# ForceBoard.net
KiCad netlist of a schematic drawn in EAGLE
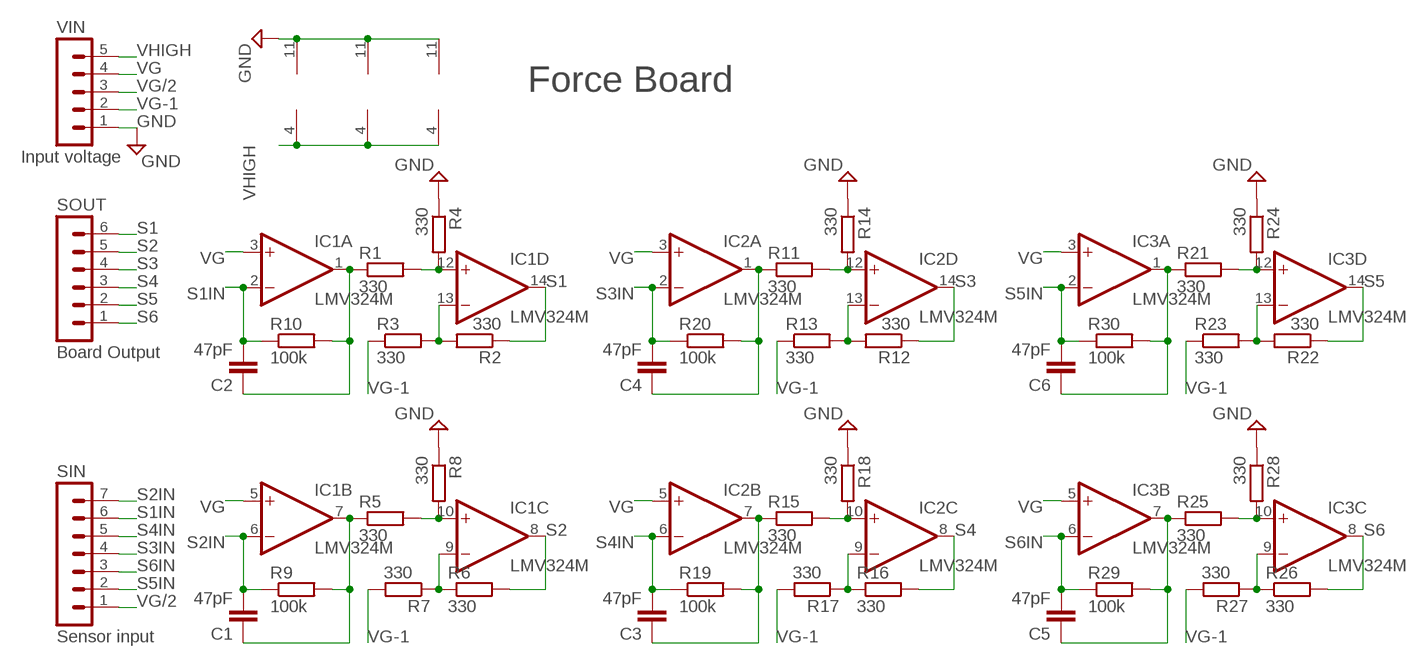
[diagram p0: schematic, sheet 1]

(export (version "E")
  (design (tool "Eeschema 10.0.6"))
  (components
    (comp (ref "C1")
      (value "47pF")
      (footprint "eagle-import:C0805")
      (libsource (lib "eagle-import") (part "C-EUC0805"))
    )
    (comp (ref "C2")
      (value "47pF")
      (footprint "eagle-import:C0805")
      (libsource (lib "eagle-import") (part "C-EUC0805"))
    )
    (comp (ref "C3")
      (value "47pF")
      (footprint "eagle-import:C0805")
      (libsource (lib "eagle-import") (part "C-EUC0805"))
    )
    (comp (ref "C4")
      (value "47pF")
      (footprint "eagle-import:C0805")
      (libsource (lib "eagle-import") (part "C-EUC0805"))
    )
    (comp (ref "C5")
      (value "47pF")
      (footprint "eagle-import:C0805")
      (libsource (lib "eagle-import") (part "C-EUC0805"))
    )
    (comp (ref "C6")
      (value "47pF")
      (footprint "eagle-import:C0805")
      (libsource (lib "eagle-import") (part "C-EUC0805"))
    )
    (comp (ref "IC1")
      (value "LMV324M")
      (footprint "eagle-import:SO14")
      (libsource (lib "eagle-import") (part "LMV324?M"))
    )
    (comp (ref "IC2")
      (value "LMV324M")
      (footprint "eagle-import:SO14")
      (libsource (lib "eagle-import") (part "LMV324?M"))
    )
    (comp (ref "IC3")
      (value "LMV324M")
      (footprint "eagle-import:SO14")
      (libsource (lib "eagle-import") (part "LMV324?M"))
    )
    (comp (ref "R1")
      (value "330")
      (footprint "eagle-import:R0805")
      (libsource (lib "eagle-import") (part "R-EU_R0805"))
    )
    (comp (ref "R2")
      (value "330")
      (footprint "eagle-import:R0805")
      (libsource (lib "eagle-import") (part "R-EU_R0805"))
    )
    (comp (ref "R3")
      (value "330")
      (footprint "eagle-import:R0805")
      (libsource (lib "eagle-import") (part "R-EU_R0805"))
    )
    (comp (ref "R4")
      (value "330")
      (footprint "eagle-import:R0805")
      (libsource (lib "eagle-import") (part "R-EU_R0805"))
    )
    (comp (ref "R5")
      (value "330")
      (footprint "eagle-import:R0805")
      (libsource (lib "eagle-import") (part "R-EU_R0805"))
    )
    (comp (ref "R6")
      (value "330")
      (footprint "eagle-import:R0805")
      (libsource (lib "eagle-import") (part "R-EU_R0805"))
    )
    (comp (ref "R7")
      (value "330")
      (footprint "eagle-import:R0805")
      (libsource (lib "eagle-import") (part "R-EU_R0805"))
    )
    (comp (ref "R8")
      (value "330")
      (footprint "eagle-import:R0805")
      (libsource (lib "eagle-import") (part "R-EU_R0805"))
    )
    (comp (ref "R9")
      (value "100k")
      (footprint "eagle-import:R0805")
      (libsource (lib "eagle-import") (part "R-EU_R0805"))
    )
    (comp (ref "R10")
      (value "100k")
      (footprint "eagle-import:R0805")
      (libsource (lib "eagle-import") (part "R-EU_R0805"))
    )
    (comp (ref "R11")
      (value "330")
      (footprint "eagle-import:R0805")
      (libsource (lib "eagle-import") (part "R-EU_R0805"))
    )
    (comp (ref "R12")
      (value "330")
      (footprint "eagle-import:R0805")
      (libsource (lib "eagle-import") (part "R-EU_R0805"))
    )
    (comp (ref "R13")
      (value "330")
      (footprint "eagle-import:R0805")
      (libsource (lib "eagle-import") (part "R-EU_R0805"))
    )
    (comp (ref "R14")
      (value "330")
      (footprint "eagle-import:R0805")
      (libsource (lib "eagle-import") (part "R-EU_R0805"))
    )
    (comp (ref "R15")
      (value "330")
      (footprint "eagle-import:R0805")
      (libsource (lib "eagle-import") (part "R-EU_R0805"))
    )
    (comp (ref "R16")
      (value "330")
      (footprint "eagle-import:R0805")
      (libsource (lib "eagle-import") (part "R-EU_R0805"))
    )
    (comp (ref "R17")
      (value "330")
      (footprint "eagle-import:R0805")
      (libsource (lib "eagle-import") (part "R-EU_R0805"))
    )
    (comp (ref "R18")
      (value "330")
      (footprint "eagle-import:R0805")
      (libsource (lib "eagle-import") (part "R-EU_R0805"))
    )
    (comp (ref "R19")
      (value "100k")
      (footprint "eagle-import:R0805")
      (libsource (lib "eagle-import") (part "R-EU_R0805"))
    )
    (comp (ref "R20")
      (value "100k")
      (footprint "eagle-import:R0805")
      (libsource (lib "eagle-import") (part "R-EU_R0805"))
    )
    (comp (ref "R21")
      (value "330")
      (footprint "eagle-import:R0805")
      (libsource (lib "eagle-import") (part "R-EU_R0805"))
    )
    (comp (ref "R22")
      (value "330")
      (footprint "eagle-import:R0805")
      (libsource (lib "eagle-import") (part "R-EU_R0805"))
    )
    (comp (ref "R23")
      (value "330")
      (footprint "eagle-import:R0805")
      (libsource (lib "eagle-import") (part "R-EU_R0805"))
    )
    (comp (ref "R24")
      (value "330")
      (footprint "eagle-import:R0805")
      (libsource (lib "eagle-import") (part "R-EU_R0805"))
    )
    (comp (ref "R25")
      (value "330")
      (footprint "eagle-import:R0805")
      (libsource (lib "eagle-import") (part "R-EU_R0805"))
    )
    (comp (ref "R26")
      (value "330")
      (footprint "eagle-import:R0805")
      (libsource (lib "eagle-import") (part "R-EU_R0805"))
    )
    (comp (ref "R27")
      (value "330")
      (footprint "eagle-import:R0805")
      (libsource (lib "eagle-import") (part "R-EU_R0805"))
    )
    (comp (ref "R28")
      (value "330")
      (footprint "eagle-import:R0805")
      (libsource (lib "eagle-import") (part "R-EU_R0805"))
    )
    (comp (ref "R29")
      (value "100k")
      (footprint "eagle-import:R0805")
      (libsource (lib "eagle-import") (part "R-EU_R0805"))
    )
    (comp (ref "R30")
      (value "100k")
      (footprint "eagle-import:R0805")
      (libsource (lib "eagle-import") (part "R-EU_R0805"))
    )
    (comp (ref "SIN")
      (value "Sensor input")
      (footprint "eagle-import:MA07-1")
      (libsource (lib "eagle-import") (part "MA07-1"))
    )
    (comp (ref "SOUT")
      (value "Board Output")
      (footprint "eagle-import:MA06-1")
      (libsource (lib "eagle-import") (part "MA06-1"))
    )
    (comp (ref "VIN")
      (value "Input voltage")
      (footprint "eagle-import:MA05-1")
      (libsource (lib "eagle-import") (part "MA05-1"))
    )
  )
  (nets
    (net (code "1") (name "/S1") (class "Default")
      (node (ref "IC1") (pin "14") (pinfunction "OUT_14") (pintype "output"))
      (node (ref "R2") (pin "1") (pinfunction "1_1") (pintype "passive"))
      (node (ref "SOUT") (pin "6") (pinfunction "6_6") (pintype "passive"))
    )
    (net (code "2") (name "/S1IN") (class "Default")
      (node (ref "C2") (pin "2") (pinfunction "2_2") (pintype "passive"))
      (node (ref "IC1") (pin "2") (pinfunction "-IN_2") (pintype "input"))
      (node (ref "R10") (pin "1") (pinfunction "1_1") (pintype "passive"))
      (node (ref "SIN") (pin "6") (pinfunction "6_6") (pintype "passive"))
    )
    (net (code "3") (name "/S2") (class "Default")
      (node (ref "IC1") (pin "8") (pinfunction "OUT_8") (pintype "output"))
      (node (ref "R6") (pin "2") (pinfunction "2_2") (pintype "passive"))
      (node (ref "SOUT") (pin "5") (pinfunction "5_5") (pintype "passive"))
    )
    (net (code "4") (name "/S2IN") (class "Default")
      (node (ref "C1") (pin "2") (pinfunction "2_2") (pintype "passive"))
      (node (ref "IC1") (pin "6") (pinfunction "-IN_6") (pintype "input"))
      (node (ref "R9") (pin "1") (pinfunction "1_1") (pintype "passive"))
      (node (ref "SIN") (pin "7") (pinfunction "7_7") (pintype "passive"))
    )
    (net (code "5") (name "/S3") (class "Default")
      (node (ref "IC2") (pin "14") (pinfunction "OUT_14") (pintype "output"))
      (node (ref "R12") (pin "1") (pinfunction "1_1") (pintype "passive"))
      (node (ref "SOUT") (pin "4") (pinfunction "4_4") (pintype "passive"))
    )
    (net (code "6") (name "/S3IN") (class "Default")
      (node (ref "C4") (pin "2") (pinfunction "2_2") (pintype "passive"))
      (node (ref "IC2") (pin "2") (pinfunction "-IN_2") (pintype "input"))
      (node (ref "R20") (pin "1") (pinfunction "1_1") (pintype "passive"))
      (node (ref "SIN") (pin "4") (pinfunction "4_4") (pintype "passive"))
    )
    (net (code "7") (name "/S4") (class "Default")
      (node (ref "IC2") (pin "8") (pinfunction "OUT_8") (pintype "output"))
      (node (ref "R16") (pin "2") (pinfunction "2_2") (pintype "passive"))
      (node (ref "SOUT") (pin "3") (pinfunction "3_3") (pintype "passive"))
    )
    (net (code "8") (name "/S4IN") (class "Default")
      (node (ref "C3") (pin "2") (pinfunction "2_2") (pintype "passive"))
      (node (ref "IC2") (pin "6") (pinfunction "-IN_6") (pintype "input"))
      (node (ref "R19") (pin "1") (pinfunction "1_1") (pintype "passive"))
      (node (ref "SIN") (pin "5") (pinfunction "5_5") (pintype "passive"))
    )
    (net (code "9") (name "/S5") (class "Default")
      (node (ref "IC3") (pin "14") (pinfunction "OUT_14") (pintype "output"))
      (node (ref "R22") (pin "1") (pinfunction "1_1") (pintype "passive"))
      (node (ref "SOUT") (pin "2") (pinfunction "2_2") (pintype "passive"))
    )
    (net (code "10") (name "/S5IN") (class "Default")
      (node (ref "C6") (pin "2") (pinfunction "2_2") (pintype "passive"))
      (node (ref "IC3") (pin "2") (pinfunction "-IN_2") (pintype "input"))
      (node (ref "R30") (pin "1") (pinfunction "1_1") (pintype "passive"))
      (node (ref "SIN") (pin "2") (pinfunction "2_2") (pintype "passive"))
    )
    (net (code "11") (name "/S6") (class "Default")
      (node (ref "IC3") (pin "8") (pinfunction "OUT_8") (pintype "output"))
      (node (ref "R26") (pin "2") (pinfunction "2_2") (pintype "passive"))
      (node (ref "SOUT") (pin "1") (pinfunction "1_1") (pintype "passive"))
    )
    (net (code "12") (name "/S6IN") (class "Default")
      (node (ref "C5") (pin "2") (pinfunction "2_2") (pintype "passive"))
      (node (ref "IC3") (pin "6") (pinfunction "-IN_6") (pintype "input"))
      (node (ref "R29") (pin "1") (pinfunction "1_1") (pintype "passive"))
      (node (ref "SIN") (pin "3") (pinfunction "3_3") (pintype "passive"))
    )
    (net (code "13") (name "/VG") (class "Default")
      (node (ref "IC1") (pin "3") (pinfunction "+IN_3") (pintype "input"))
      (node (ref "IC1") (pin "5") (pinfunction "+IN_5") (pintype "input"))
      (node (ref "IC2") (pin "3") (pinfunction "+IN_3") (pintype "input"))
      (node (ref "IC2") (pin "5") (pinfunction "+IN_5") (pintype "input"))
      (node (ref "IC3") (pin "3") (pinfunction "+IN_3") (pintype "input"))
      (node (ref "IC3") (pin "5") (pinfunction "+IN_5") (pintype "input"))
      (node (ref "VIN") (pin "4") (pinfunction "4_4") (pintype "passive"))
    )
    (net (code "14") (name "/VG-1") (class "Default")
      (node (ref "R13") (pin "1") (pinfunction "1_1") (pintype "passive"))
      (node (ref "R17") (pin "2") (pinfunction "2_2") (pintype "passive"))
      (node (ref "R23") (pin "1") (pinfunction "1_1") (pintype "passive"))
      (node (ref "R27") (pin "2") (pinfunction "2_2") (pintype "passive"))
      (node (ref "R3") (pin "1") (pinfunction "1_1") (pintype "passive"))
      (node (ref "R7") (pin "2") (pinfunction "2_2") (pintype "passive"))
      (node (ref "VIN") (pin "2") (pinfunction "2_2") (pintype "passive"))
    )
    (net (code "15") (name "/VG{slash}2") (class "Default")
      (node (ref "SIN") (pin "1") (pinfunction "1_1") (pintype "passive"))
      (node (ref "VIN") (pin "3") (pinfunction "3_3") (pintype "passive"))
    )
    (net (code "16") (name "/VHIGH") (class "Default")
      (node (ref "IC1") (pin "4") (pinfunction "V+_4") (pintype "power_in"))
      (node (ref "IC2") (pin "4") (pinfunction "V+_4") (pintype "power_in"))
      (node (ref "IC3") (pin "4") (pinfunction "V+_4") (pintype "power_in"))
      (node (ref "VIN") (pin "5") (pinfunction "5_5") (pintype "passive"))
    )
    (net (code "17") (name "GND") (class "Default")
      (node (ref "IC1") (pin "11") (pinfunction "V-_11") (pintype "power_in"))
      (node (ref "IC2") (pin "11") (pinfunction "V-_11") (pintype "power_in"))
      (node (ref "IC3") (pin "11") (pinfunction "V-_11") (pintype "power_in"))
      (node (ref "R14") (pin "1") (pinfunction "1_1") (pintype "passive"))
      (node (ref "R18") (pin "1") (pinfunction "1_1") (pintype "passive"))
      (node (ref "R24") (pin "1") (pinfunction "1_1") (pintype "passive"))
      (node (ref "R28") (pin "1") (pinfunction "1_1") (pintype "passive"))
      (node (ref "R4") (pin "1") (pinfunction "1_1") (pintype "passive"))
      (node (ref "R8") (pin "1") (pinfunction "1_1") (pintype "passive"))
      (node (ref "VIN") (pin "1") (pinfunction "1_1") (pintype "passive"))
    )
    (net (code "18") (name "Net-(IC1A-OUT)") (class "Default")
      (node (ref "C2") (pin "1") (pinfunction "1_1") (pintype "passive"))
      (node (ref "IC1") (pin "1") (pinfunction "OUT_1") (pintype "output"))
      (node (ref "R1") (pin "1") (pinfunction "1_1") (pintype "passive"))
      (node (ref "R10") (pin "2") (pinfunction "2_2") (pintype "passive"))
    )
    (net (code "19") (name "Net-(IC1B-OUT)") (class "Default")
      (node (ref "C1") (pin "1") (pinfunction "1_1") (pintype "passive"))
      (node (ref "IC1") (pin "7") (pinfunction "OUT_7") (pintype "output"))
      (node (ref "R5") (pin "1") (pinfunction "1_1") (pintype "passive"))
      (node (ref "R9") (pin "2") (pinfunction "2_2") (pintype "passive"))
    )
    (net (code "20") (name "Net-(IC1C-+IN)") (class "Default")
      (node (ref "IC1") (pin "10") (pinfunction "+IN_10") (pintype "input"))
      (node (ref "R5") (pin "2") (pinfunction "2_2") (pintype "passive"))
      (node (ref "R8") (pin "2") (pinfunction "2_2") (pintype "passive"))
    )
    (net (code "21") (name "Net-(IC1C--IN)") (class "Default")
      (node (ref "IC1") (pin "9") (pinfunction "-IN_9") (pintype "input"))
      (node (ref "R6") (pin "1") (pinfunction "1_1") (pintype "passive"))
      (node (ref "R7") (pin "1") (pinfunction "1_1") (pintype "passive"))
    )
    (net (code "22") (name "Net-(IC1D-+IN)") (class "Default")
      (node (ref "IC1") (pin "12") (pinfunction "+IN_12") (pintype "input"))
      (node (ref "R1") (pin "2") (pinfunction "2_2") (pintype "passive"))
      (node (ref "R4") (pin "2") (pinfunction "2_2") (pintype "passive"))
    )
    (net (code "23") (name "Net-(IC1D--IN)") (class "Default")
      (node (ref "IC1") (pin "13") (pinfunction "-IN_13") (pintype "input"))
      (node (ref "R2") (pin "2") (pinfunction "2_2") (pintype "passive"))
      (node (ref "R3") (pin "2") (pinfunction "2_2") (pintype "passive"))
    )
    (net (code "24") (name "Net-(IC2A-OUT)") (class "Default")
      (node (ref "C4") (pin "1") (pinfunction "1_1") (pintype "passive"))
      (node (ref "IC2") (pin "1") (pinfunction "OUT_1") (pintype "output"))
      (node (ref "R11") (pin "1") (pinfunction "1_1") (pintype "passive"))
      (node (ref "R20") (pin "2") (pinfunction "2_2") (pintype "passive"))
    )
    (net (code "25") (name "Net-(IC2B-OUT)") (class "Default")
      (node (ref "C3") (pin "1") (pinfunction "1_1") (pintype "passive"))
      (node (ref "IC2") (pin "7") (pinfunction "OUT_7") (pintype "output"))
      (node (ref "R15") (pin "1") (pinfunction "1_1") (pintype "passive"))
      (node (ref "R19") (pin "2") (pinfunction "2_2") (pintype "passive"))
    )
    (net (code "26") (name "Net-(IC2C-+IN)") (class "Default")
      (node (ref "IC2") (pin "10") (pinfunction "+IN_10") (pintype "input"))
      (node (ref "R15") (pin "2") (pinfunction "2_2") (pintype "passive"))
      (node (ref "R18") (pin "2") (pinfunction "2_2") (pintype "passive"))
    )
    (net (code "27") (name "Net-(IC2C--IN)") (class "Default")
      (node (ref "IC2") (pin "9") (pinfunction "-IN_9") (pintype "input"))
      (node (ref "R16") (pin "1") (pinfunction "1_1") (pintype "passive"))
      (node (ref "R17") (pin "1") (pinfunction "1_1") (pintype "passive"))
    )
    (net (code "28") (name "Net-(IC2D-+IN)") (class "Default")
      (node (ref "IC2") (pin "12") (pinfunction "+IN_12") (pintype "input"))
      (node (ref "R11") (pin "2") (pinfunction "2_2") (pintype "passive"))
      (node (ref "R14") (pin "2") (pinfunction "2_2") (pintype "passive"))
    )
    (net (code "29") (name "Net-(IC2D--IN)") (class "Default")
      (node (ref "IC2") (pin "13") (pinfunction "-IN_13") (pintype "input"))
      (node (ref "R12") (pin "2") (pinfunction "2_2") (pintype "passive"))
      (node (ref "R13") (pin "2") (pinfunction "2_2") (pintype "passive"))
    )
    (net (code "30") (name "Net-(IC3A-OUT)") (class "Default")
      (node (ref "C6") (pin "1") (pinfunction "1_1") (pintype "passive"))
      (node (ref "IC3") (pin "1") (pinfunction "OUT_1") (pintype "output"))
      (node (ref "R21") (pin "1") (pinfunction "1_1") (pintype "passive"))
      (node (ref "R30") (pin "2") (pinfunction "2_2") (pintype "passive"))
    )
    (net (code "31") (name "Net-(IC3B-OUT)") (class "Default")
      (node (ref "C5") (pin "1") (pinfunction "1_1") (pintype "passive"))
      (node (ref "IC3") (pin "7") (pinfunction "OUT_7") (pintype "output"))
      (node (ref "R25") (pin "1") (pinfunction "1_1") (pintype "passive"))
      (node (ref "R29") (pin "2") (pinfunction "2_2") (pintype "passive"))
    )
    (net (code "32") (name "Net-(IC3C-+IN)") (class "Default")
      (node (ref "IC3") (pin "10") (pinfunction "+IN_10") (pintype "input"))
      (node (ref "R25") (pin "2") (pinfunction "2_2") (pintype "passive"))
      (node (ref "R28") (pin "2") (pinfunction "2_2") (pintype "passive"))
    )
    (net (code "33") (name "Net-(IC3C--IN)") (class "Default")
      (node (ref "IC3") (pin "9") (pinfunction "-IN_9") (pintype "input"))
      (node (ref "R26") (pin "1") (pinfunction "1_1") (pintype "passive"))
      (node (ref "R27") (pin "1") (pinfunction "1_1") (pintype "passive"))
    )
    (net (code "34") (name "Net-(IC3D-+IN)") (class "Default")
      (node (ref "IC3") (pin "12") (pinfunction "+IN_12") (pintype "input"))
      (node (ref "R21") (pin "2") (pinfunction "2_2") (pintype "passive"))
      (node (ref "R24") (pin "2") (pinfunction "2_2") (pintype "passive"))
    )
    (net (code "35") (name "Net-(IC3D--IN)") (class "Default")
      (node (ref "IC3") (pin "13") (pinfunction "-IN_13") (pintype "input"))
      (node (ref "R22") (pin "2") (pinfunction "2_2") (pintype "passive"))
      (node (ref "R23") (pin "2") (pinfunction "2_2") (pintype "passive"))
    )
  )
)
